# TPS56339_3_3V_1A.net
KiCad netlist of a schematic drawn in Altium Designer
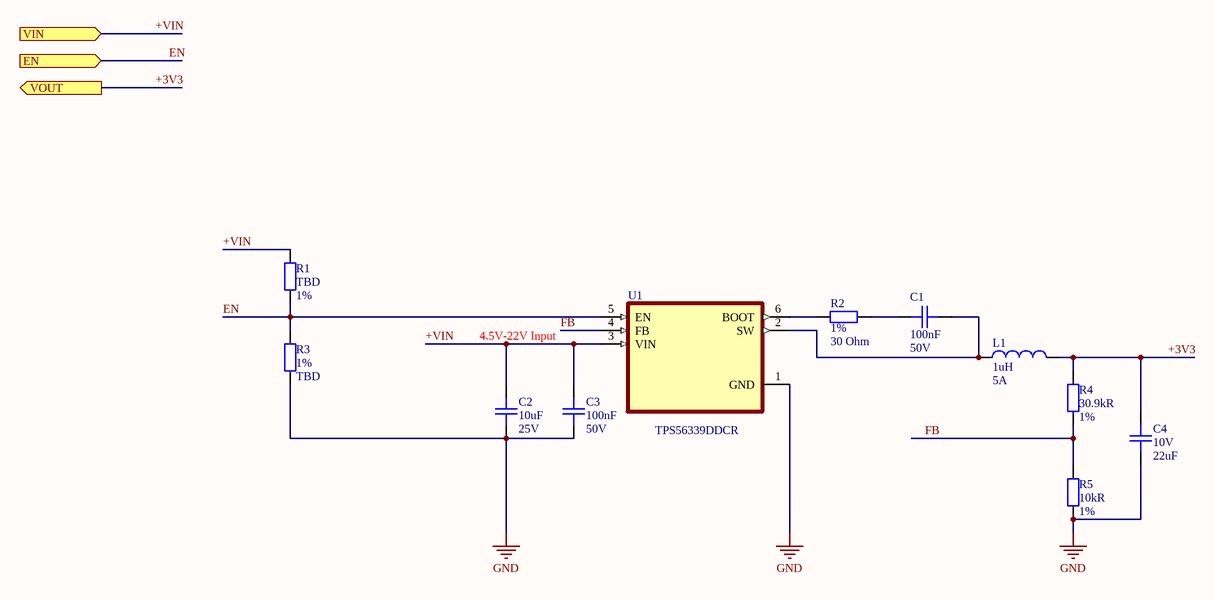
[diagram p0: TPS56339_3.3V_1A.SchDoc]

(export (version "E")
  (design (tool "Eeschema 10.0.6"))
  (components
    (comp (ref "C1")
      (value "CAP CER 0.1UF 50V X7R 0402")
      (footprint "C0402")
      (description "0.1µF ±10% 50V Ceramic Capacitor X7R 0402 (1005 Metric)")
      (fields
        (field (name "MANUFACTURER") "TDK")
        (field (name "MANUFACTURER PART NUMBER") "CGA2B3X7R1H104K050BB")
        (field (name "CAPACITANCE") "100nF")
        (field (name "VOLTAGE") "50V")
      )
      (libsource (lib "Control_Board_Model_C201") (part "CAP CER 0.1UF 50V X7R 0402"))
    )
    (comp (ref "C2")
      (value "CAP CER 10UF 25V X7R 1206")
      (footprint "C1206")
      (description "10µF ±10% 25V Ceramic Capacitor X7R 1206 (3216 Metric)")
      (fields
        (field (name "MANUFACTURER") "Yageo")
        (field (name "MANUFACTURER PART NUMBER") "CC1206KKX7R8BB106")
        (field (name "CAPACITANCE") "10uF")
        (field (name "VOLTAGE RATING") "25V")
      )
      (libsource (lib "Control_Board_Model_C201") (part "CAP CER 10UF 25V X7R 1206"))
    )
    (comp (ref "C3")
      (value "CAP CER 0.1UF 50V X7R 0402")
      (footprint "C0402")
      (description "0.1µF ±10% 50V Ceramic Capacitor X7R 0402 (1005 Metric)")
      (fields
        (field (name "MANUFACTURER") "TDK")
        (field (name "MANUFACTURER PART NUMBER") "CGA2B3X7R1H104K050BB")
        (field (name "CAPACITANCE") "100nF")
        (field (name "VOLTAGE") "50V")
      )
      (libsource (lib "Control_Board_Model_C201") (part "CAP CER 0.1UF 50V X7R 0402"))
    )
    (comp (ref "C4")
      (value "CAP CER 22UF 10V X5R 0805")
      (footprint "C0805")
      (description "22µF ±20% 10V Ceramic Capacitor X5R 0805 (2012 Metric)")
      (fields
        (field (name "MANUFACTURER") "Taiyo Yuden")
        (field (name "MANUFACTURER PART NUMBER") "LMK212BJ226MG-T")
        (field (name "VOLTAGE RATING") "10V")
        (field (name "CAPACITANCE") "22uF")
      )
      (libsource (lib "Control_Board_Model_C201") (part "CAP CER 22UF 10V X5R 0805"))
    )
    (comp (ref "L1")
      (value "FIXED IND 1UH 5A 24 MOHM SMD")
      (footprint "IND_IHLP-1212B00")
      (description "1µH Shielded Molded Inductor 5A 24mOhm Max Nonstandard")
      (fields
        (field (name "MANUFACTURER") "Vishay Dale")
        (field (name "MANUFACTURER PART NUMBER") "IHLP1212BZER1R0M11")
        (field (name "INDUCTANCE") "1uH")
        (field (name "CURRENT RATING") "5A")
      )
      (libsource (lib "Control_Board_Model_C201") (part "FIXED IND 1UH 5A 24 MOHM SMD"))
    )
    (comp (ref "R1")
      (value "DNP")
      (footprint "R0402")
      (description "4.75 kOhms ±1% 0.063W, 1/16W Chip Resistor 0402 (1005 Metric) Moisture Resistant Thick Film")
      (fields
        (field (name "MANUFACTURER") "Yageo")
        (field (name "MANUFACTURER PART NUMBER") "RC0402FR-074K75P")
        (field (name "RESISTANCE") "TBD")
        (field (name "TOLERANCE") "1%")
      )
      (libsource (lib "Control_Board_Model_C201") (part "RES SMD 4.75K OHM 1% 1/16W 0402"))
    )
    (comp (ref "R2")
      (value "RES SMD 30 OHM 1% 1/10W 0402")
      (footprint "R0402")
      (fields
        (field (name "MANUFACTURER PART NUMBER") "ERJ-2GEJ300X")
        (field (name "MANUFACTURER") "Panasonic")
        (field (name "TOLERANCE") "1%")
        (field (name "RESISTANCE") "30 Ohm")
      )
      (libsource (lib "Control_Board_Model_C201") (part "RES SMD 10 OHM 1% 1/16W 0402"))
    )
    (comp (ref "R3")
      (value "DNP")
      (footprint "R0402")
      (fields
        (field (name "MANUFACTURER") "Yageo")
        (field (name "MANUFACTURER PART NUMBER") "RC0402FR-075K1L")
        (field (name "TOLERANCE") "1%")
        (field (name "RESISTANCE") "TBD")
      )
      (libsource (lib "Control_Board_Model_C201") (part "RES SMD 5.1K OHM 1% 1/16W 0402"))
    )
    (comp (ref "R4")
      (value "RES SMD 30.9K OHM 1% 1/10W 0402")
      (footprint "R0402")
      (description "30.9 kOhms ±1% 0.100W, 1/10W Chip Resistor 0402 (1005 Metric) Moisture Resistant Thick Film")
      (fields
        (field (name "MANUFACTURER PART NUMBER") "RP73PF1E30K9BTD")
        (field (name "MANUFACTURER") "Yageo")
        (field (name "RESISTANCE") "30.9kR")
        (field (name "TOLERANCE") "1%")
      )
      (libsource (lib "Control_Board_Model_C201") (part "RES SMD 10K OHM 1% 1/16W 0402"))
    )
    (comp (ref "R5")
      (value "RES SMD 10K OHM 1% 1/16W 0402")
      (footprint "R0402")
      (description "10 kOhms ±1% 0.063W, 1/16W Chip Resistor 0402 (1005 Metric) Moisture Resistant Thick Film")
      (fields
        (field (name "MANUFACTURER") "Yageo")
        (field (name "MANUFACTURER PART NUMBER") "RC0402FR-0710KP")
        (field (name "RESISTANCE") "10kR")
        (field (name "TOLERANCE") "1%")
      )
      (libsource (lib "") (part "RES SMD 10K OHM 1% 1/16W 0402_1"))
    )
    (comp (ref "U1")
      (value "TPS56339DDCR")
      (footprint "SOT95P280X110-6N")
      (description "4.5-V to 24-V input, 3-A output synchronous buck converter 6-SOT-23-THIN -40 to 125")
      (fields (field (name "MF") "Texas Instruments"))
      (libsource (lib "TPS56339DDCR") (part "TPS56339DDCR"))
    )
  )
  (nets
    (net (code "1") (name "/+3V3") (class "Default")
      (node (ref "C4") (pin "2") (pinfunction "2_2") (pintype "passive"))
      (node (ref "L1") (pin "2") (pinfunction "2_2") (pintype "passive"))
      (node (ref "R4") (pin "2") (pinfunction "2_2") (pintype "passive"))
    )
    (net (code "2") (name "/+VIN") (class "Default")
      (node (ref "C2") (pin "2") (pinfunction "2_2") (pintype "passive"))
      (node (ref "C3") (pin "2") (pinfunction "2_2") (pintype "passive"))
      (node (ref "R1") (pin "2") (pinfunction "2_2") (pintype "passive"))
      (node (ref "U1") (pin "3") (pinfunction "VIN_3") (pintype "input"))
    )
    (net (code "3") (name "/EN") (class "Default")
      (node (ref "R1") (pin "1") (pinfunction "1_1") (pintype "passive"))
      (node (ref "R3") (pin "2") (pinfunction "2_2") (pintype "passive"))
      (node (ref "U1") (pin "5") (pinfunction "EN_5") (pintype "input"))
    )
    (net (code "4") (name "/FB") (class "Default")
      (node (ref "R4") (pin "1") (pinfunction "1_1") (pintype "passive"))
      (node (ref "R5") (pin "1") (pinfunction "1_1") (pintype "passive"))
      (node (ref "U1") (pin "4") (pinfunction "FB_4") (pintype "input"))
    )
    (net (code "5") (name "GND") (class "Default")
      (node (ref "C2") (pin "1") (pinfunction "1_1") (pintype "passive"))
      (node (ref "C3") (pin "1") (pinfunction "1_1") (pintype "passive"))
      (node (ref "C4") (pin "1") (pinfunction "1_1") (pintype "passive"))
      (node (ref "R3") (pin "1") (pinfunction "1_1") (pintype "passive"))
      (node (ref "R5") (pin "2") (pinfunction "2_2") (pintype "passive"))
      (node (ref "U1") (pin "1") (pinfunction "GND_1") (pintype "power_in"))
    )
    (net (code "6") (name "Net-(C1-Pad1)") (class "Default")
      (node (ref "C1") (pin "1") (pinfunction "1_1") (pintype "passive"))
      (node (ref "R2") (pin "2") (pinfunction "2_2") (pintype "passive"))
    )
    (net (code "7") (name "Net-(U1-BOOT)") (class "Default")
      (node (ref "R2") (pin "1") (pinfunction "1_1") (pintype "passive"))
      (node (ref "U1") (pin "6") (pinfunction "BOOT_6") (pintype "output"))
    )
    (net (code "8") (name "Net-(U1-SW)") (class "Default")
      (node (ref "C1") (pin "2") (pinfunction "2_2") (pintype "passive"))
      (node (ref "L1") (pin "1") (pinfunction "1_1") (pintype "passive"))
      (node (ref "U1") (pin "2") (pinfunction "SW_2") (pintype "output"))
    )
  )
)
